# sampling.net
KiCad netlist of a schematic drawn in EAGLE
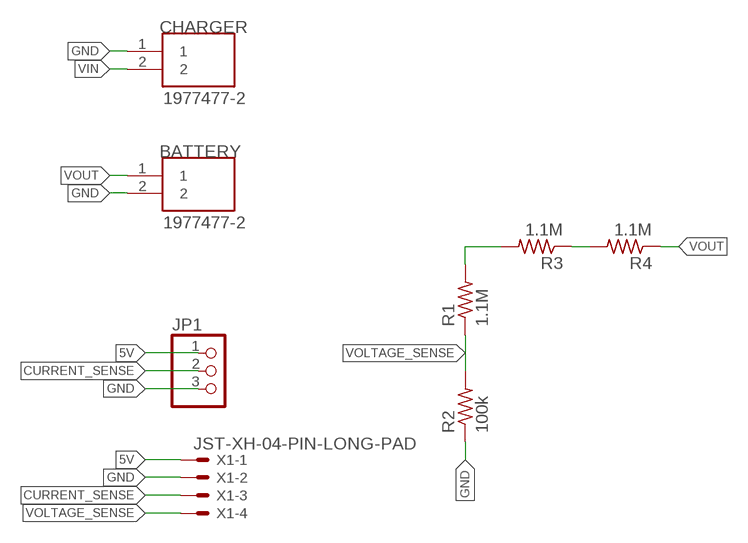
[diagram p0: schematic, sheet 1]

(export (version "E")
  (design (tool "Eeschema 10.0.6"))
  (components
    (comp (ref "BATTERY")
      (value "1977477-2")
      (footprint "eagle-import:TE_1977477-2")
      (fields (field (name "MF") "TE Connectivity"))
      (libsource (lib "eagle-import") (part "1977477-2"))
    )
    (comp (ref "CHARGER")
      (value "1977477-2")
      (footprint "eagle-import:TE_1977477-2")
      (fields (field (name "MF") "TE Connectivity"))
      (libsource (lib "eagle-import") (part "1977477-2"))
    )
    (comp (ref "JP1")
      (value "PINHD-1X3")
      (footprint "eagle-import:1X03")
      (libsource (lib "eagle-import") (part "PINHD-1X3"))
    )
    (comp (ref "R1")
      (value "1.1M")
      (footprint "eagle-import:R0805")
      (libsource (lib "eagle-import") (part "R-US_R0805"))
    )
    (comp (ref "R2")
      (value "100k")
      (footprint "eagle-import:R0805")
      (libsource (lib "eagle-import") (part "R-US_R0805"))
    )
    (comp (ref "R3")
      (value "1.1M")
      (footprint "eagle-import:R0805")
      (libsource (lib "eagle-import") (part "R-US_R0805"))
    )
    (comp (ref "R4")
      (value "1.1M")
      (footprint "eagle-import:R0805")
      (libsource (lib "eagle-import") (part "R-US_R0805"))
    )
    (comp (ref "X1")
      (value "JST-XH-04-PIN-LONG-PAD")
      (footprint "eagle-import:JST-XH-04-PACKAGE-LONG-PAD")
      (libsource (lib "eagle-import") (part "JST-XH-04-PIN-LONG-PAD"))
    )
  )
  (nets
    (net (code "1") (name "5V") (class "Default")
      (node (ref "JP1") (pin "1") (pinfunction "1_1") (pintype "passive"))
      (node (ref "X1") (pin "1") (pinfunction "S_1") (pintype "passive"))
    )
    (net (code "2") (name "CURRENT_SENSE") (class "Default")
      (node (ref "JP1") (pin "2") (pinfunction "2_2") (pintype "passive"))
      (node (ref "X1") (pin "3") (pinfunction "S_3") (pintype "passive"))
    )
    (net (code "3") (name "GND") (class "Default")
      (node (ref "BATTERY") (pin "2") (pinfunction "2_2") (pintype "passive"))
      (node (ref "CHARGER") (pin "1") (pinfunction "1_1") (pintype "passive"))
      (node (ref "JP1") (pin "3") (pinfunction "3_3") (pintype "passive"))
      (node (ref "R2") (pin "1") (pinfunction "1_1") (pintype "passive"))
      (node (ref "X1") (pin "2") (pinfunction "S_2") (pintype "passive"))
    )
    (net (code "4") (name "Net-(R1-Pad2)") (class "Default")
      (node (ref "R1") (pin "2") (pinfunction "2_2") (pintype "passive"))
      (node (ref "R3") (pin "2") (pinfunction "2_2") (pintype "passive"))
    )
    (net (code "5") (name "Net-(R3-Pad1)") (class "Default")
      (node (ref "R3") (pin "1") (pinfunction "1_1") (pintype "passive"))
      (node (ref "R4") (pin "2") (pinfunction "2_2") (pintype "passive"))
    )
    (net (code "6") (name "VIN") (class "Default")
      (node (ref "CHARGER") (pin "2") (pinfunction "2_2") (pintype "passive"))
    )
    (net (code "7") (name "VOLTAGE_SENSE") (class "Default")
      (node (ref "R1") (pin "1") (pinfunction "1_1") (pintype "passive"))
      (node (ref "R2") (pin "2") (pinfunction "2_2") (pintype "passive"))
      (node (ref "X1") (pin "4") (pinfunction "S_4") (pintype "passive"))
    )
    (net (code "8") (name "VOUT") (class "Default")
      (node (ref "BATTERY") (pin "1") (pinfunction "1_1") (pintype "passive"))
      (node (ref "R4") (pin "1") (pinfunction "1_1") (pintype "passive"))
    )
  )
)
